# circuit_2023-05-02.net
KiCad netlist of a schematic drawn in Altium Designer
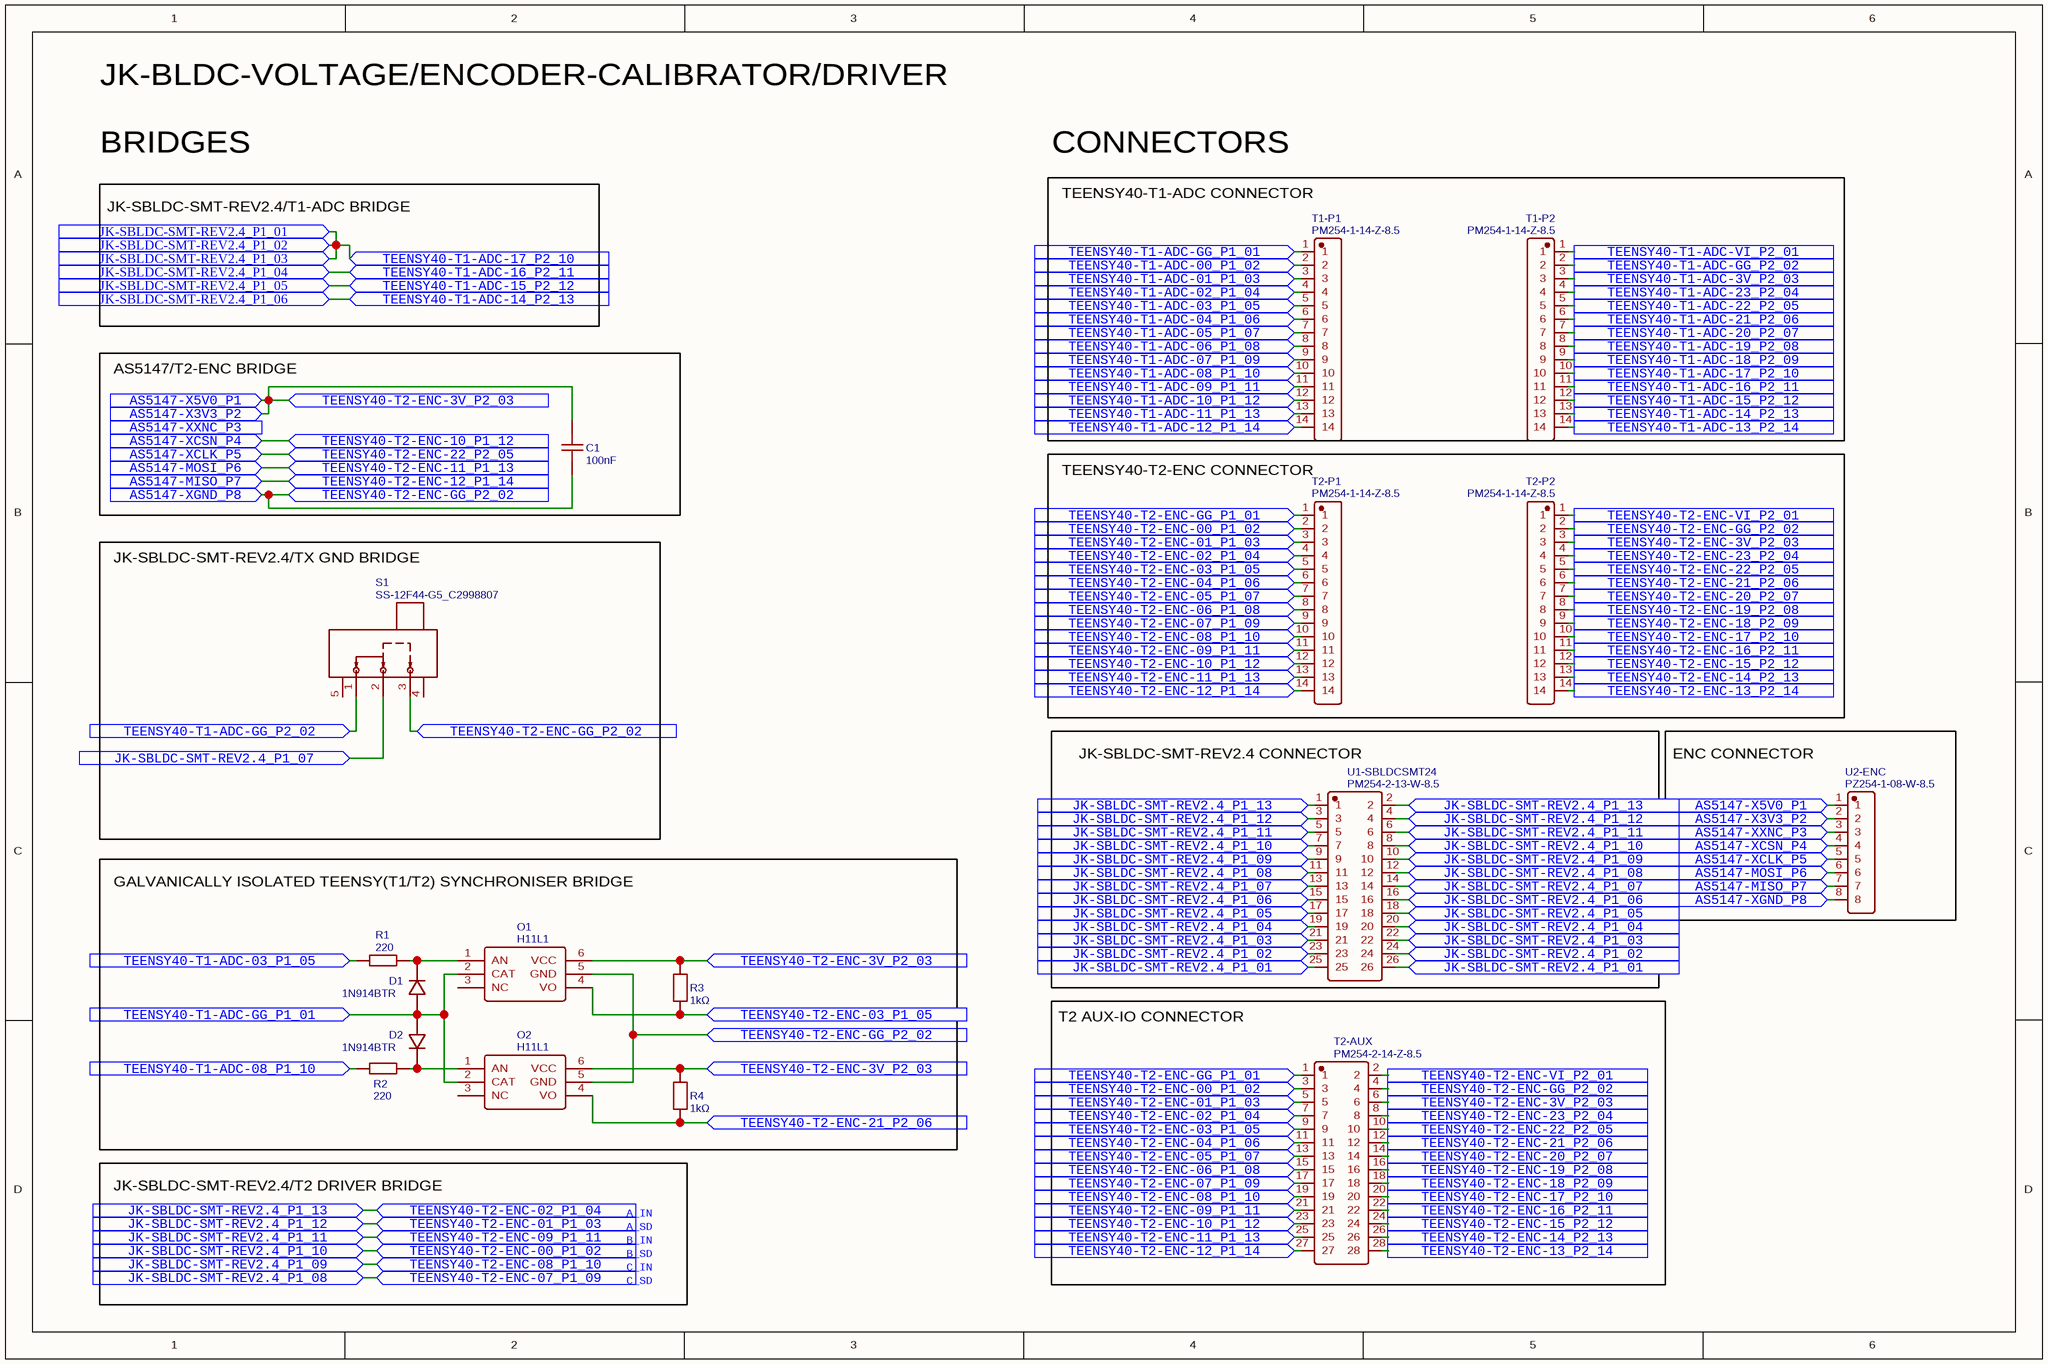
[diagram p0: circuit_2023-05-02.schdoc]

(export (version "E")
  (design (tool "Eeschema 10.0.6"))
  (components
    (comp (ref "C1")
      (value "100nF")
      (fields
        (field (name "BOM_SUPPLIER PART") "C254109")
        (field (name "BOM_MANUFACTURER PART") "CC2A104ZC1ID3F7C30MF")
        (field (name "CONTRIBUTOR") "LCSC")
      )
      (libsource (lib "altium-import") (part "root_3_100nF_"))
    )
    (comp (ref "D1")
      (value "1N914BTR")
      (fields (field (name "BOM_SUPPLIER PART") "C258180") (field (name "CONTRIBUTOR") "LCSC"))
      (libsource (lib "altium-import") (part "root_3_1N914BTR_"))
    )
    (comp (ref "D2")
      (value "1N914BTR")
      (fields (field (name "BOM_SUPPLIER PART") "C258180") (field (name "CONTRIBUTOR") "LCSC"))
      (libsource (lib "altium-import") (part "root_1_1N914BTR_"))
    )
    (comp (ref "O1")
      (value "H11L1")
      (fields (field (name "BOM_SUPPLIER PART") "C78588"))
      (libsource (lib "altium-import") (part "root_0_H11L1_"))
    )
    (comp (ref "O2")
      (value "H11L1")
      (fields (field (name "BOM_SUPPLIER PART") "C78588"))
      (libsource (lib "altium-import") (part "root_0_H11L1_"))
    )
    (comp (ref "R1")
      (value "220")
      (fields
        (field (name "BOM_SUPPLIER PART") "C172985")
        (field (name "BOM_MANUFACTURER PART") "MFR-25FTE52-220R")
        (field (name "CONTRIBUTOR") "LCSC")
      )
      (libsource (lib "altium-import") (part "root_0_220_"))
    )
    (comp (ref "R2")
      (value "220")
      (fields
        (field (name "BOM_SUPPLIER PART") "C172985")
        (field (name "BOM_MANUFACTURER PART") "MFR-25FTE52-220R")
        (field (name "CONTRIBUTOR") "LCSC")
      )
      (libsource (lib "altium-import") (part "root_0_220_"))
    )
    (comp (ref "R3")
      (value "1kΩ")
      (fields
        (field (name "BOM_SUPPLIER PART") "C713997")
        (field (name "BOM_MANUFACTURER PART") "MF1/4W-1KΩ±1%T52")
        (field (name "CONTRIBUTOR") "LCSC")
      )
      (libsource (lib "altium-import") (part "root_3_1kΩ_"))
    )
    (comp (ref "R4")
      (value "1kΩ")
      (fields
        (field (name "BOM_SUPPLIER PART") "C713997")
        (field (name "BOM_MANUFACTURER PART") "MF1/4W-1KΩ±1%T52")
        (field (name "CONTRIBUTOR") "LCSC")
      )
      (libsource (lib "altium-import") (part "root_3_1kΩ_"))
    )
    (comp (ref "S1")
      (value "SS-12F44-G5_C2998807")
      (fields
        (field (name "BOM_SUPPLIER PART") "C2998807")
        (field (name "BOM_MANUFACTURER PART") "SS-12F44-G5")
        (field (name "CONTRIBUTOR") "lcsc")
      )
      (libsource (lib "altium-import") (part "root_0_SS-12F44-G5_C2998807_"))
    )
    (comp (ref "T1-P1")
      (value "PM254-1-14-Z-8.5")
      (fields (field (name "BOM_SUPPLIER PART") "C2897377") (field (name "CONTRIBUTOR") "LCSC"))
      (libsource (lib "") (part "root_0_PM254-1-14-Z-8.5__1"))
    )
    (comp (ref "T1-P2")
      (value "PM254-1-14-Z-8.5")
      (fields (field (name "BOM_SUPPLIER PART") "C2897377") (field (name "CONTRIBUTOR") "LCSC"))
      (libsource (lib "altium-import") (part "root_0_PM254-1-14-Z-8.5_"))
    )
    (comp (ref "T2-AUX")
      (value "PM254-2-14-Z-8.5")
      (fields (field (name "BOM_SUPPLIER PART") "C2897415") (field (name "CONTRIBUTOR") "LCSC"))
      (libsource (lib "altium-import") (part "root_0_PM254-2-14-Z-8.5_"))
    )
    (comp (ref "T2-P1")
      (value "PM254-1-14-Z-8.5")
      (fields (field (name "BOM_SUPPLIER PART") "C2897377") (field (name "CONTRIBUTOR") "LCSC"))
      (libsource (lib "") (part "root_0_PM254-1-14-Z-8.5__1"))
    )
    (comp (ref "T2-P2")
      (value "PM254-1-14-Z-8.5")
      (fields (field (name "BOM_SUPPLIER PART") "C2897377") (field (name "CONTRIBUTOR") "LCSC"))
      (libsource (lib "altium-import") (part "root_0_PM254-1-14-Z-8.5_"))
    )
    (comp (ref "U1-SBLDCSMT24")
      (value "PM254-2-13-W-8.5")
      (fields (field (name "BOM_SUPPLIER PART") "C2897433") (field (name "CONTRIBUTOR") "LCSC"))
      (libsource (lib "altium-import") (part "root_0_PM254-2-13-W-8.5_"))
    )
    (comp (ref "U2-ENC")
      (value "PZ254-1-08-W-8.5")
      (fields (field (name "BOM_SUPPLIER PART") "C2894950") (field (name "CONTRIBUTOR") "LCSC"))
      (libsource (lib "altium-import") (part "root_0_PZ254-1-08-W-8.5_"))
    )
  )
  (nets
    (net (code "1") (name "/AS5147-MISO_P7") (class "Default")
      (node (ref "T2-AUX") (pin "27") (pinfunction "27_27") (pintype "passive"))
      (node (ref "T2-P1") (pin "14") (pinfunction "14_14") (pintype "passive"))
      (node (ref "U2-ENC") (pin "7") (pinfunction "7_7") (pintype "passive"))
    )
    (net (code "2") (name "/AS5147-MOSI_P6") (class "Default")
      (node (ref "T2-AUX") (pin "25") (pinfunction "25_25") (pintype "passive"))
      (node (ref "T2-P1") (pin "13") (pinfunction "13_13") (pintype "passive"))
      (node (ref "U2-ENC") (pin "6") (pinfunction "6_6") (pintype "passive"))
    )
    (net (code "3") (name "/AS5147-X3V3_P2") (class "Default")
      (node (ref "C1") (pin "1") (pinfunction "1_1") (pintype "passive"))
      (node (ref "O1") (pin "6") (pinfunction "VCC_6") (pintype "passive"))
      (node (ref "O2") (pin "6") (pinfunction "VCC_6") (pintype "passive"))
      (node (ref "R3") (pin "1") (pinfunction "1_1") (pintype "passive"))
      (node (ref "R4") (pin "1") (pinfunction "1_1") (pintype "passive"))
      (node (ref "T2-AUX") (pin "6") (pinfunction "6_6") (pintype "passive"))
      (node (ref "T2-P2") (pin "3") (pinfunction "3_3") (pintype "passive"))
      (node (ref "U2-ENC") (pin "1") (pinfunction "1_1") (pintype "passive"))
      (node (ref "U2-ENC") (pin "2") (pinfunction "2_2") (pintype "passive"))
    )
    (net (code "4") (name "/AS5147-XCLK_P5") (class "Default")
      (node (ref "T2-AUX") (pin "10") (pinfunction "10_10") (pintype "passive"))
      (node (ref "T2-P2") (pin "5") (pinfunction "5_5") (pintype "passive"))
      (node (ref "U2-ENC") (pin "5") (pinfunction "5_5") (pintype "passive"))
    )
    (net (code "5") (name "/AS5147-XCSN_P4") (class "Default")
      (node (ref "T2-AUX") (pin "23") (pinfunction "23_23") (pintype "passive"))
      (node (ref "T2-P1") (pin "12") (pinfunction "12_12") (pintype "passive"))
      (node (ref "U2-ENC") (pin "4") (pinfunction "4_4") (pintype "passive"))
    )
    (net (code "6") (name "/AS5147-XGND_P8") (class "Default")
      (node (ref "C1") (pin "2") (pinfunction "2_2") (pintype "passive"))
      (node (ref "O1") (pin "5") (pinfunction "GND_5") (pintype "passive"))
      (node (ref "O2") (pin "5") (pinfunction "GND_5") (pintype "passive"))
      (node (ref "S1") (pin "3") (pinfunction "3_3") (pintype "passive"))
      (node (ref "T2-AUX") (pin "4") (pinfunction "4_4") (pintype "passive"))
      (node (ref "T2-P2") (pin "2") (pinfunction "2_2") (pintype "passive"))
      (node (ref "U2-ENC") (pin "8") (pinfunction "8_8") (pintype "passive"))
    )
    (net (code "7") (name "/AS5147-XXNC_P3") (class "Default")
      (node (ref "U2-ENC") (pin "3") (pinfunction "3_3") (pintype "passive"))
    )
    (net (code "8") (name "/JK-SBLDC-SMT-REV2.4_P1_01") (class "Default")
      (node (ref "T1-P2") (pin "10") (pinfunction "10_10") (pintype "passive"))
      (node (ref "U1-SBLDCSMT24") (pin "21") (pinfunction "21_21") (pintype "passive"))
      (node (ref "U1-SBLDCSMT24") (pin "22") (pinfunction "22_22") (pintype "passive"))
      (node (ref "U1-SBLDCSMT24") (pin "23") (pinfunction "23_23") (pintype "passive"))
      (node (ref "U1-SBLDCSMT24") (pin "24") (pinfunction "24_24") (pintype "passive"))
      (node (ref "U1-SBLDCSMT24") (pin "25") (pinfunction "25_25") (pintype "passive"))
      (node (ref "U1-SBLDCSMT24") (pin "26") (pinfunction "26_26") (pintype "passive"))
    )
    (net (code "9") (name "/JK-SBLDC-SMT-REV2.4_P1_04") (class "Default")
      (node (ref "T1-P2") (pin "11") (pinfunction "11_11") (pintype "passive"))
      (node (ref "U1-SBLDCSMT24") (pin "19") (pinfunction "19_19") (pintype "passive"))
      (node (ref "U1-SBLDCSMT24") (pin "20") (pinfunction "20_20") (pintype "passive"))
    )
    (net (code "10") (name "/JK-SBLDC-SMT-REV2.4_P1_05") (class "Default")
      (node (ref "T1-P2") (pin "12") (pinfunction "12_12") (pintype "passive"))
      (node (ref "U1-SBLDCSMT24") (pin "17") (pinfunction "17_17") (pintype "passive"))
      (node (ref "U1-SBLDCSMT24") (pin "18") (pinfunction "18_18") (pintype "passive"))
    )
    (net (code "11") (name "/JK-SBLDC-SMT-REV2.4_P1_06") (class "Default")
      (node (ref "T1-P2") (pin "13") (pinfunction "13_13") (pintype "passive"))
      (node (ref "U1-SBLDCSMT24") (pin "15") (pinfunction "15_15") (pintype "passive"))
      (node (ref "U1-SBLDCSMT24") (pin "16") (pinfunction "16_16") (pintype "passive"))
    )
    (net (code "12") (name "/JK-SBLDC-SMT-REV2.4_P1_07") (class "Default")
      (node (ref "S1") (pin "2") (pinfunction "2_2") (pintype "passive"))
      (node (ref "U1-SBLDCSMT24") (pin "13") (pinfunction "13_13") (pintype "passive"))
      (node (ref "U1-SBLDCSMT24") (pin "14") (pinfunction "14_14") (pintype "passive"))
    )
    (net (code "13") (name "/JK-SBLDC-SMT-REV2.4_P1_08") (class "Default")
      (node (ref "T2-AUX") (pin "17") (pinfunction "17_17") (pintype "passive"))
      (node (ref "T2-P1") (pin "9") (pinfunction "9_9") (pintype "passive"))
      (node (ref "U1-SBLDCSMT24") (pin "11") (pinfunction "11_11") (pintype "passive"))
      (node (ref "U1-SBLDCSMT24") (pin "12") (pinfunction "12_12") (pintype "passive"))
    )
    (net (code "14") (name "/JK-SBLDC-SMT-REV2.4_P1_09") (class "Default")
      (node (ref "T2-AUX") (pin "19") (pinfunction "19_19") (pintype "passive"))
      (node (ref "T2-P1") (pin "10") (pinfunction "10_10") (pintype "passive"))
      (node (ref "U1-SBLDCSMT24") (pin "10") (pinfunction "10_10") (pintype "passive"))
      (node (ref "U1-SBLDCSMT24") (pin "9") (pinfunction "9_9") (pintype "passive"))
    )
    (net (code "15") (name "/JK-SBLDC-SMT-REV2.4_P1_10") (class "Default")
      (node (ref "T2-AUX") (pin "3") (pinfunction "3_3") (pintype "passive"))
      (node (ref "T2-P1") (pin "2") (pinfunction "2_2") (pintype "passive"))
      (node (ref "U1-SBLDCSMT24") (pin "7") (pinfunction "7_7") (pintype "passive"))
      (node (ref "U1-SBLDCSMT24") (pin "8") (pinfunction "8_8") (pintype "passive"))
    )
    (net (code "16") (name "/JK-SBLDC-SMT-REV2.4_P1_11") (class "Default")
      (node (ref "T2-AUX") (pin "21") (pinfunction "21_21") (pintype "passive"))
      (node (ref "T2-P1") (pin "11") (pinfunction "11_11") (pintype "passive"))
      (node (ref "U1-SBLDCSMT24") (pin "5") (pinfunction "5_5") (pintype "passive"))
      (node (ref "U1-SBLDCSMT24") (pin "6") (pinfunction "6_6") (pintype "passive"))
    )
    (net (code "17") (name "/JK-SBLDC-SMT-REV2.4_P1_12") (class "Default")
      (node (ref "T2-AUX") (pin "5") (pinfunction "5_5") (pintype "passive"))
      (node (ref "T2-P1") (pin "3") (pinfunction "3_3") (pintype "passive"))
      (node (ref "U1-SBLDCSMT24") (pin "3") (pinfunction "3_3") (pintype "passive"))
      (node (ref "U1-SBLDCSMT24") (pin "4") (pinfunction "4_4") (pintype "passive"))
    )
    (net (code "18") (name "/JK-SBLDC-SMT-REV2.4_P1_13") (class "Default")
      (node (ref "T2-AUX") (pin "7") (pinfunction "7_7") (pintype "passive"))
      (node (ref "T2-P1") (pin "4") (pinfunction "4_4") (pintype "passive"))
      (node (ref "U1-SBLDCSMT24") (pin "1") (pinfunction "1_1") (pintype "passive"))
      (node (ref "U1-SBLDCSMT24") (pin "2") (pinfunction "2_2") (pintype "passive"))
    )
    (net (code "19") (name "/TEENSY40-T1-ADC-00_P1_02") (class "Default")
      (node (ref "T1-P1") (pin "2") (pinfunction "2_2") (pintype "passive"))
    )
    (net (code "20") (name "/TEENSY40-T1-ADC-01_P1_03") (class "Default")
      (node (ref "T1-P1") (pin "3") (pinfunction "3_3") (pintype "passive"))
    )
    (net (code "21") (name "/TEENSY40-T1-ADC-02_P1_04") (class "Default")
      (node (ref "T1-P1") (pin "4") (pinfunction "4_4") (pintype "passive"))
    )
    (net (code "22") (name "/TEENSY40-T1-ADC-3V_P2_03") (class "Default")
      (node (ref "T1-P2") (pin "3") (pinfunction "3_3") (pintype "passive"))
    )
    (net (code "23") (name "/TEENSY40-T1-ADC-03_P1_05") (class "Default")
      (node (ref "R1") (pin "1") (pinfunction "1_1") (pintype "passive"))
      (node (ref "T1-P1") (pin "5") (pinfunction "5_5") (pintype "passive"))
    )
    (net (code "24") (name "/TEENSY40-T1-ADC-04_P1_06") (class "Default")
      (node (ref "T1-P1") (pin "6") (pinfunction "6_6") (pintype "passive"))
    )
    (net (code "25") (name "/TEENSY40-T1-ADC-05_P1_07") (class "Default")
      (node (ref "T1-P1") (pin "7") (pinfunction "7_7") (pintype "passive"))
    )
    (net (code "26") (name "/TEENSY40-T1-ADC-06_P1_08") (class "Default")
      (node (ref "T1-P1") (pin "8") (pinfunction "8_8") (pintype "passive"))
    )
    (net (code "27") (name "/TEENSY40-T1-ADC-07_P1_09") (class "Default")
      (node (ref "T1-P1") (pin "9") (pinfunction "9_9") (pintype "passive"))
    )
    (net (code "28") (name "/TEENSY40-T1-ADC-08_P1_10") (class "Default")
      (node (ref "R2") (pin "1") (pinfunction "1_1") (pintype "passive"))
      (node (ref "T1-P1") (pin "10") (pinfunction "10_10") (pintype "passive"))
    )
    (net (code "29") (name "/TEENSY40-T1-ADC-09_P1_11") (class "Default")
      (node (ref "T1-P1") (pin "11") (pinfunction "11_11") (pintype "passive"))
    )
    (net (code "30") (name "/TEENSY40-T1-ADC-10_P1_12") (class "Default")
      (node (ref "T1-P1") (pin "12") (pinfunction "12_12") (pintype "passive"))
    )
    (net (code "31") (name "/TEENSY40-T1-ADC-11_P1_13") (class "Default")
      (node (ref "T1-P1") (pin "13") (pinfunction "13_13") (pintype "passive"))
    )
    (net (code "32") (name "/TEENSY40-T1-ADC-12_P1_14") (class "Default")
      (node (ref "T1-P1") (pin "14") (pinfunction "14_14") (pintype "passive"))
    )
    (net (code "33") (name "/TEENSY40-T1-ADC-13_P2_14") (class "Default")
      (node (ref "T1-P2") (pin "14") (pinfunction "14_14") (pintype "passive"))
    )
    (net (code "34") (name "/TEENSY40-T1-ADC-18_P2_09") (class "Default")
      (node (ref "T1-P2") (pin "9") (pinfunction "9_9") (pintype "passive"))
    )
    (net (code "35") (name "/TEENSY40-T1-ADC-19_P2_08") (class "Default")
      (node (ref "T1-P2") (pin "8") (pinfunction "8_8") (pintype "passive"))
    )
    (net (code "36") (name "/TEENSY40-T1-ADC-20_P2_07") (class "Default")
      (node (ref "T1-P2") (pin "7") (pinfunction "7_7") (pintype "passive"))
    )
    (net (code "37") (name "/TEENSY40-T1-ADC-21_P2_06") (class "Default")
      (node (ref "T1-P2") (pin "6") (pinfunction "6_6") (pintype "passive"))
    )
    (net (code "38") (name "/TEENSY40-T1-ADC-22_P2_05") (class "Default")
      (node (ref "T1-P2") (pin "5") (pinfunction "5_5") (pintype "passive"))
    )
    (net (code "39") (name "/TEENSY40-T1-ADC-23_P2_04") (class "Default")
      (node (ref "T1-P2") (pin "4") (pinfunction "4_4") (pintype "passive"))
    )
    (net (code "40") (name "/TEENSY40-T1-ADC-GG_P1_01") (class "Default")
      (node (ref "D1") (pin "2") (pinfunction "2_2") (pintype "passive"))
      (node (ref "D2") (pin "2") (pinfunction "2_2") (pintype "passive"))
      (node (ref "O1") (pin "2") (pinfunction "CAT_2") (pintype "passive"))
      (node (ref "O2") (pin "2") (pinfunction "CAT_2") (pintype "passive"))
      (node (ref "T1-P1") (pin "1") (pinfunction "1_1") (pintype "passive"))
    )
    (net (code "41") (name "/TEENSY40-T1-ADC-GG_P2_02") (class "Default")
      (node (ref "S1") (pin "1") (pinfunction "1_1") (pintype "passive"))
      (node (ref "T1-P2") (pin "2") (pinfunction "2_2") (pintype "passive"))
    )
    (net (code "42") (name "/TEENSY40-T1-ADC-VI_P2_01") (class "Default")
      (node (ref "T1-P2") (pin "1") (pinfunction "1_1") (pintype "passive"))
    )
    (net (code "43") (name "/TEENSY40-T2-ENC-03_P1_05") (class "Default")
      (node (ref "O1") (pin "4") (pinfunction "VO_4") (pintype "passive"))
      (node (ref "R3") (pin "2") (pinfunction "2_2") (pintype "passive"))
      (node (ref "T2-AUX") (pin "9") (pinfunction "9_9") (pintype "passive"))
      (node (ref "T2-P1") (pin "5") (pinfunction "5_5") (pintype "passive"))
    )
    (net (code "44") (name "/TEENSY40-T2-ENC-04_P1_06") (class "Default")
      (node (ref "T2-AUX") (pin "11") (pinfunction "11_11") (pintype "passive"))
      (node (ref "T2-P1") (pin "6") (pinfunction "6_6") (pintype "passive"))
    )
    (net (code "45") (name "/TEENSY40-T2-ENC-05_P1_07") (class "Default")
      (node (ref "T2-AUX") (pin "13") (pinfunction "13_13") (pintype "passive"))
      (node (ref "T2-P1") (pin "7") (pinfunction "7_7") (pintype "passive"))
    )
    (net (code "46") (name "/TEENSY40-T2-ENC-06_P1_08") (class "Default")
      (node (ref "T2-AUX") (pin "15") (pinfunction "15_15") (pintype "passive"))
      (node (ref "T2-P1") (pin "8") (pinfunction "8_8") (pintype "passive"))
    )
    (net (code "47") (name "/TEENSY40-T2-ENC-13_P2_14") (class "Default")
      (node (ref "T2-AUX") (pin "28") (pinfunction "28_28") (pintype "passive"))
      (node (ref "T2-P2") (pin "14") (pinfunction "14_14") (pintype "passive"))
    )
    (net (code "48") (name "/TEENSY40-T2-ENC-14_P2_13") (class "Default")
      (node (ref "T2-AUX") (pin "26") (pinfunction "26_26") (pintype "passive"))
      (node (ref "T2-P2") (pin "13") (pinfunction "13_13") (pintype "passive"))
    )
    (net (code "49") (name "/TEENSY40-T2-ENC-15_P2_12") (class "Default")
      (node (ref "T2-AUX") (pin "24") (pinfunction "24_24") (pintype "passive"))
      (node (ref "T2-P2") (pin "12") (pinfunction "12_12") (pintype "passive"))
    )
    (net (code "50") (name "/TEENSY40-T2-ENC-16_P2_11") (class "Default")
      (node (ref "T2-AUX") (pin "22") (pinfunction "22_22") (pintype "passive"))
      (node (ref "T2-P2") (pin "11") (pinfunction "11_11") (pintype "passive"))
    )
    (net (code "51") (name "/TEENSY40-T2-ENC-17_P2_10") (class "Default")
      (node (ref "T2-AUX") (pin "20") (pinfunction "20_20") (pintype "passive"))
      (node (ref "T2-P2") (pin "10") (pinfunction "10_10") (pintype "passive"))
    )
    (net (code "52") (name "/TEENSY40-T2-ENC-18_P2_09") (class "Default")
      (node (ref "T2-AUX") (pin "18") (pinfunction "18_18") (pintype "passive"))
      (node (ref "T2-P2") (pin "9") (pinfunction "9_9") (pintype "passive"))
    )
    (net (code "53") (name "/TEENSY40-T2-ENC-19_P2_08") (class "Default")
      (node (ref "T2-AUX") (pin "16") (pinfunction "16_16") (pintype "passive"))
      (node (ref "T2-P2") (pin "8") (pinfunction "8_8") (pintype "passive"))
    )
    (net (code "54") (name "/TEENSY40-T2-ENC-20_P2_07") (class "Default")
      (node (ref "T2-AUX") (pin "14") (pinfunction "14_14") (pintype "passive"))
      (node (ref "T2-P2") (pin "7") (pinfunction "7_7") (pintype "passive"))
    )
    (net (code "55") (name "/TEENSY40-T2-ENC-21_P2_06") (class "Default")
      (node (ref "O2") (pin "4") (pinfunction "VO_4") (pintype "passive"))
      (node (ref "R4") (pin "2") (pinfunction "2_2") (pintype "passive"))
      (node (ref "T2-AUX") (pin "12") (pinfunction "12_12") (pintype "passive"))
      (node (ref "T2-P2") (pin "6") (pinfunction "6_6") (pintype "passive"))
    )
    (net (code "56") (name "/TEENSY40-T2-ENC-23_P2_04") (class "Default")
      (node (ref "T2-AUX") (pin "8") (pinfunction "8_8") (pintype "passive"))
      (node (ref "T2-P2") (pin "4") (pinfunction "4_4") (pintype "passive"))
    )
    (net (code "57") (name "/TEENSY40-T2-ENC-GG_P1_01") (class "Default")
      (node (ref "T2-AUX") (pin "1") (pinfunction "1_1") (pintype "passive"))
      (node (ref "T2-P1") (pin "1") (pinfunction "1_1") (pintype "passive"))
    )
    (net (code "58") (name "/TEENSY40-T2-ENC-VI_P2_01") (class "Default")
      (node (ref "T2-AUX") (pin "2") (pinfunction "2_2") (pintype "passive"))
      (node (ref "T2-P2") (pin "1") (pinfunction "1_1") (pintype "passive"))
    )
    (net (code "59") (name "Net-(O1-AN)") (class "Default")
      (node (ref "D1") (pin "1") (pinfunction "1_1") (pintype "passive"))
      (node (ref "O1") (pin "1") (pinfunction "AN_1") (pintype "passive"))
      (node (ref "R1") (pin "2") (pinfunction "2_2") (pintype "passive"))
    )
    (net (code "60") (name "Net-(O2-AN)") (class "Default")
      (node (ref "D2") (pin "1") (pinfunction "1_1") (pintype "passive"))
      (node (ref "O2") (pin "1") (pinfunction "AN_1") (pintype "passive"))
      (node (ref "R2") (pin "2") (pinfunction "2_2") (pintype "passive"))
    )
    (net (code "61") (name "unconnected-(O1-NC-Pad3)") (class "Default")
      (node (ref "O1") (pin "3") (pinfunction "NC_3") (pintype "passive"))
    )
    (net (code "62") (name "unconnected-(O2-NC-Pad3)") (class "Default")
      (node (ref "O2") (pin "3") (pinfunction "NC_3") (pintype "passive"))
    )
    (net (code "63") (name "unconnected-(S1-Pad4)") (class "Default")
      (node (ref "S1") (pin "4") (pinfunction "4_4") (pintype "passive"))
    )
    (net (code "64") (name "unconnected-(S1-Pad5)") (class "Default")
      (node (ref "S1") (pin "5") (pinfunction "5_5") (pintype "passive"))
    )
  )
)
